# wifi_sensor.net
KiCad netlist of a schematic drawn in Altium Designer
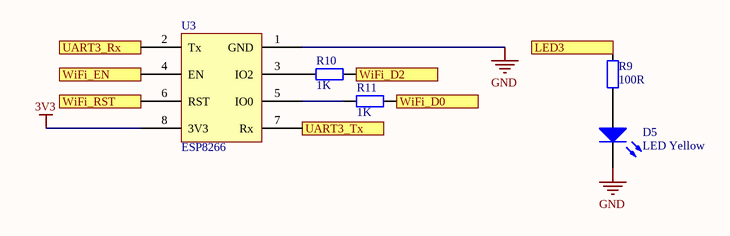
[diagram p0: wifi_sensor.SchDoc]

(export (version "E")
  (design (tool "Eeschema 10.0.6"))
  (components
    (comp (ref "D5")
      (value "LED Yellow")
      (footprint "FP_0805_LED_RED")
      (description "Yellow LED")
      (libsource (lib "hallglib") (part "LED Yellow"))
    )
    (comp (ref "R9")
      (value "100R")
      (footprint "FP_0805_RES")
      (description "Resistor")
      (fields (field (name "TOLERANCE") "5%") (field (name "POWER") "125mW"))
      (libsource (lib "hallglib") (part "RES 100R"))
    )
    (comp (ref "R10")
      (value "1K")
      (footprint "FP_0805_RES")
      (description "Resistor")
      (fields (field (name "TOLERANCE") "5%") (field (name "POWER") "125mW"))
      (libsource (lib "hallglib") (part "RES 1K"))
    )
    (comp (ref "R11")
      (value "1K")
      (footprint "FP_0805_RES")
      (description "Resistor")
      (fields (field (name "TOLERANCE") "5%") (field (name "POWER") "125mW"))
      (libsource (lib "hallglib") (part "RES 1K"))
    )
    (comp (ref "U3") (value "ESP8266") (footprint "HDR2X4") (libsource (lib "qlib") (part "ESP8266")))
  )
  (nets
    (net (code "1") (name "/LED3") (class "Default")
      (node (ref "R9") (pin "2") (pinfunction "2_2") (pintype "passive"))
    )
    (net (code "2") (name "/UART3_Rx") (class "Default")
      (node (ref "U3") (pin "2") (pinfunction "Tx_2") (pintype "passive"))
    )
    (net (code "3") (name "/UART3_Tx") (class "Default")
      (node (ref "U3") (pin "7") (pinfunction "Rx_7") (pintype "passive"))
    )
    (net (code "4") (name "/WiFi_D0") (class "Default")
      (node (ref "R11") (pin "2") (pinfunction "2_2") (pintype "passive"))
    )
    (net (code "5") (name "/WiFi_D2") (class "Default")
      (node (ref "R10") (pin "2") (pinfunction "2_2") (pintype "passive"))
    )
    (net (code "6") (name "/WiFi_EN") (class "Default")
      (node (ref "U3") (pin "4") (pinfunction "EN_4") (pintype "passive"))
    )
    (net (code "7") (name "/WiFi_RST") (class "Default")
      (node (ref "U3") (pin "6") (pinfunction "RST_6") (pintype "passive"))
    )
    (net (code "8") (name "3V3") (class "Default")
      (node (ref "U3") (pin "8") (pinfunction "3V3_8") (pintype "passive"))
    )
    (net (code "9") (name "GND") (class "Default")
      (node (ref "D5") (pin "2") (pinfunction "K_2") (pintype "passive"))
      (node (ref "U3") (pin "1") (pinfunction "GND_1") (pintype "passive"))
    )
    (net (code "10") (name "Net-(D5-A)") (class "Default")
      (node (ref "D5") (pin "1") (pinfunction "A_1") (pintype "passive"))
      (node (ref "R9") (pin "1") (pinfunction "1_1") (pintype "passive"))
    )
    (net (code "11") (name "Net-(U3-IO0)") (class "Default")
      (node (ref "R11") (pin "1") (pinfunction "1_1") (pintype "passive"))
      (node (ref "U3") (pin "5") (pinfunction "IO0_5") (pintype "passive"))
    )
    (net (code "12") (name "Net-(U3-IO2)") (class "Default")
      (node (ref "R10") (pin "1") (pinfunction "1_1") (pintype "passive"))
      (node (ref "U3") (pin "3") (pinfunction "IO2_3") (pintype "passive"))
    )
  )
)
